# trig2_board.net
KiCad netlist of a schematic drawn in EAGLE
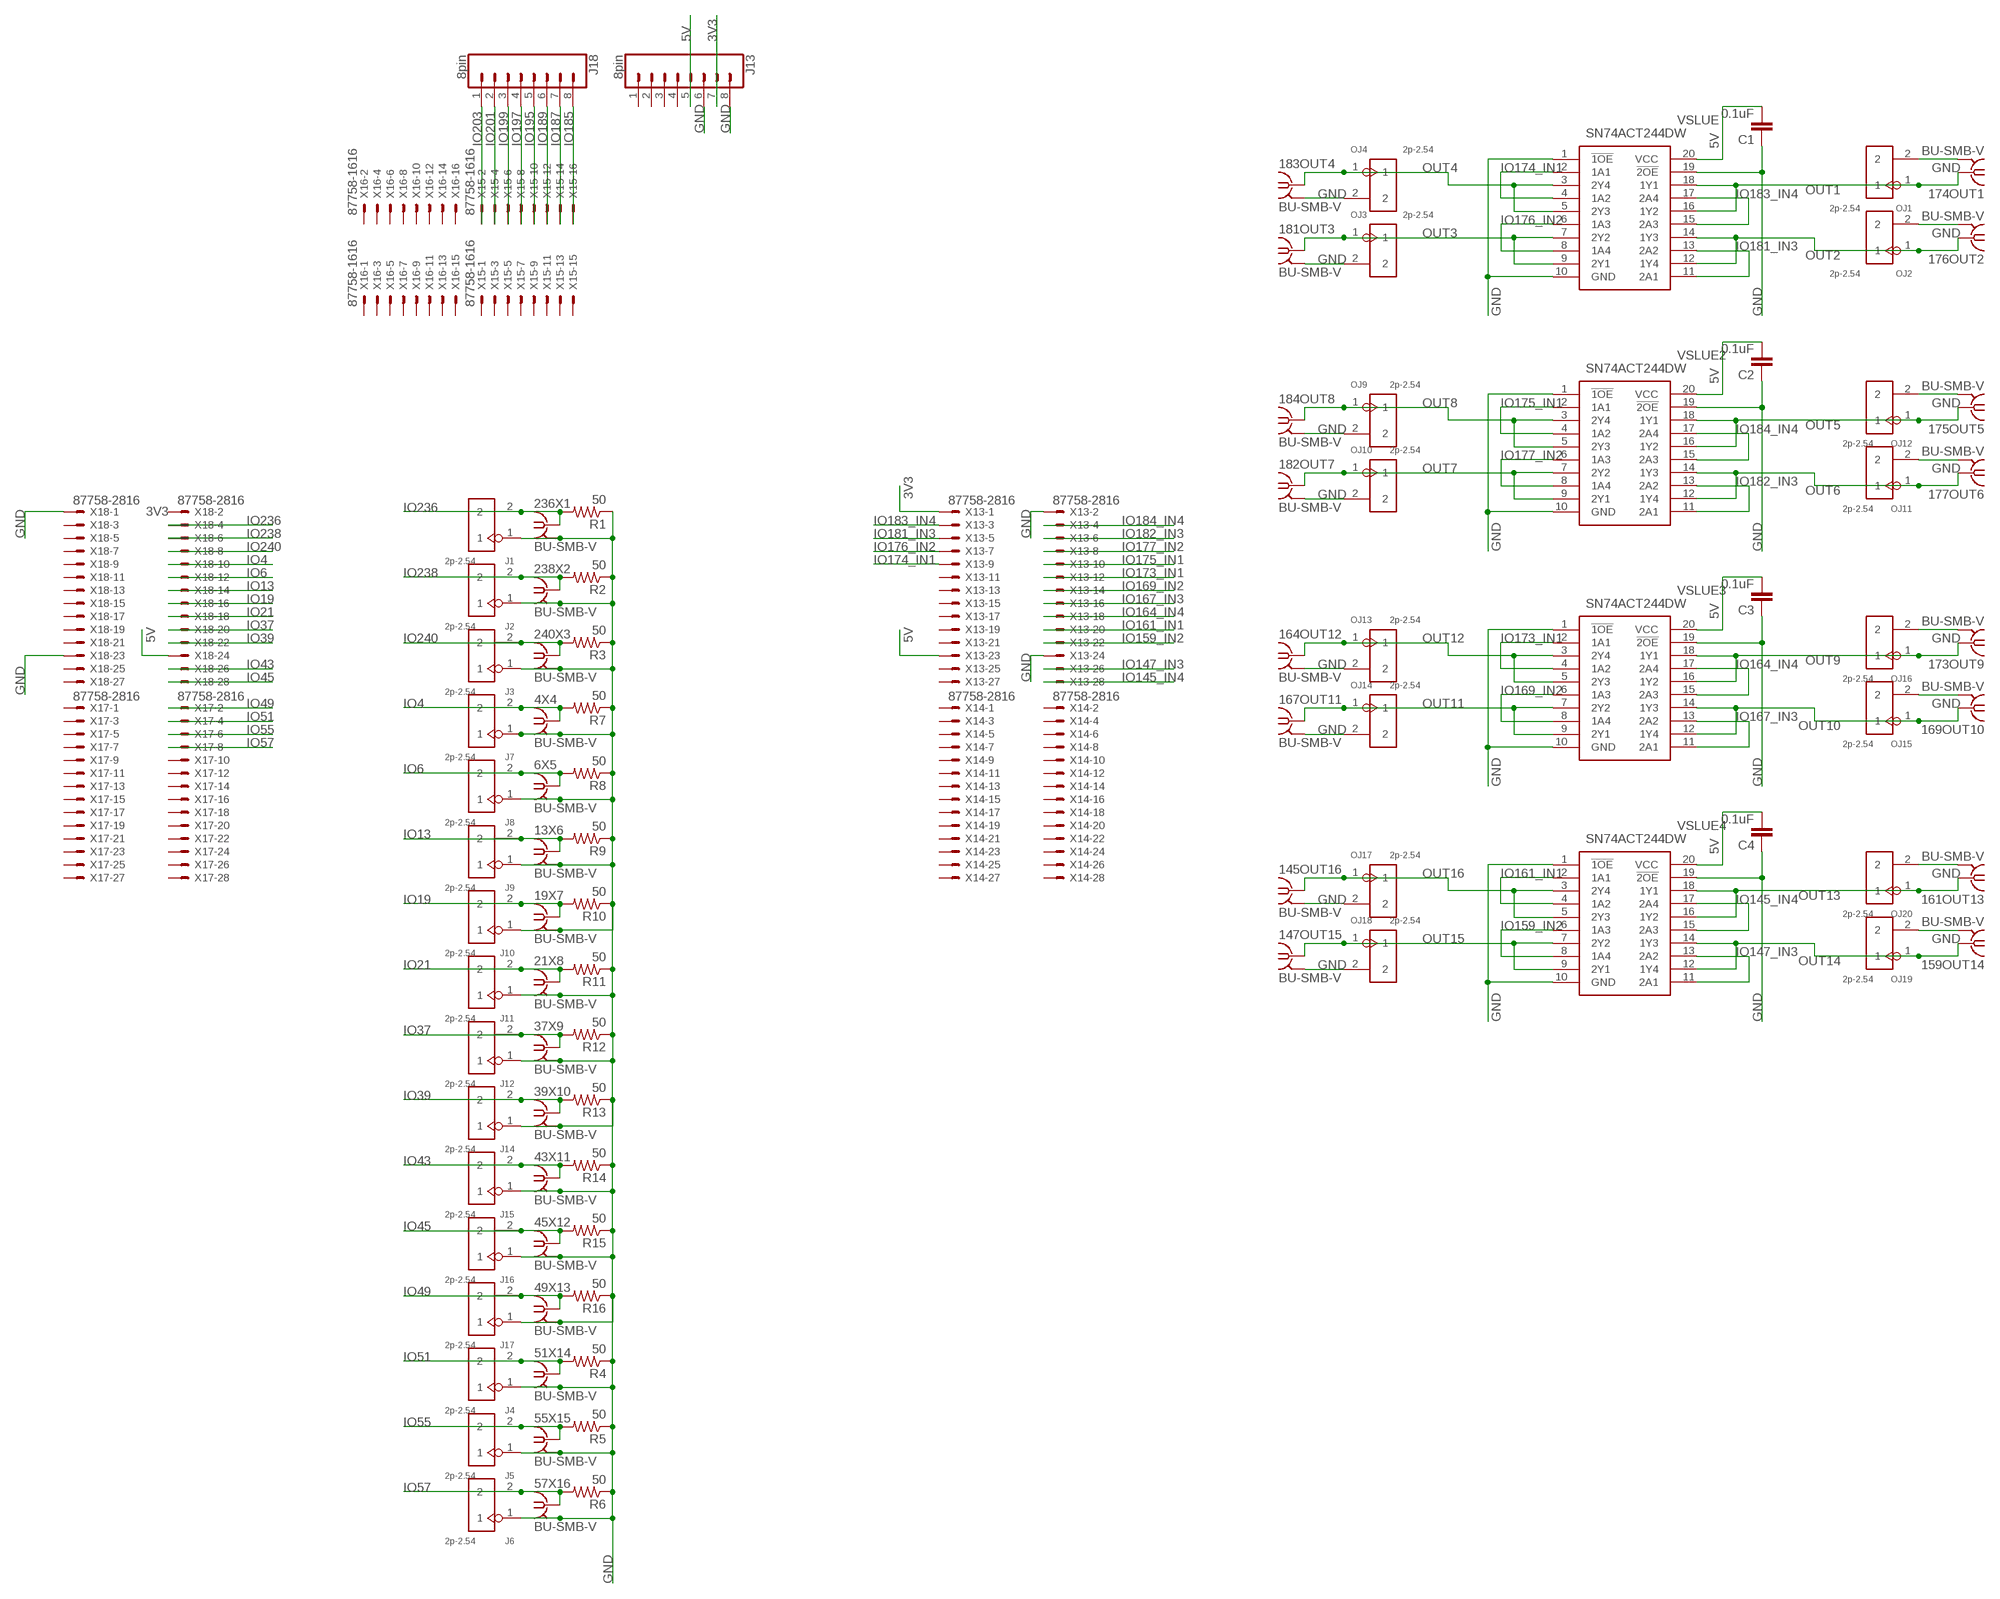
[diagram p0: schematic, sheet 1]

(export (version "E")
  (design (tool "Eeschema 10.0.6"))
  (components
    (comp (ref "4X4")
      (value "BU-SMB-V")
      (footprint "eagle-import:BU-SMB-V")
      (libsource (lib "eagle-import") (part "BU-SMB-V"))
    )
    (comp (ref "6X5")
      (value "BU-SMB-V")
      (footprint "eagle-import:BU-SMB-V")
      (libsource (lib "eagle-import") (part "BU-SMB-V"))
    )
    (comp (ref "13X6")
      (value "BU-SMB-V")
      (footprint "eagle-import:BU-SMB-V")
      (libsource (lib "eagle-import") (part "BU-SMB-V"))
    )
    (comp (ref "19X7")
      (value "BU-SMB-V")
      (footprint "eagle-import:BU-SMB-V")
      (libsource (lib "eagle-import") (part "BU-SMB-V"))
    )
    (comp (ref "21X8")
      (value "BU-SMB-V")
      (footprint "eagle-import:BU-SMB-V")
      (libsource (lib "eagle-import") (part "BU-SMB-V"))
    )
    (comp (ref "37X9")
      (value "BU-SMB-V")
      (footprint "eagle-import:BU-SMB-V")
      (libsource (lib "eagle-import") (part "BU-SMB-V"))
    )
    (comp (ref "39X10")
      (value "BU-SMB-V")
      (footprint "eagle-import:BU-SMB-V")
      (libsource (lib "eagle-import") (part "BU-SMB-V"))
    )
    (comp (ref "43X11")
      (value "BU-SMB-V")
      (footprint "eagle-import:BU-SMB-V")
      (libsource (lib "eagle-import") (part "BU-SMB-V"))
    )
    (comp (ref "45X12")
      (value "BU-SMB-V")
      (footprint "eagle-import:BU-SMB-V")
      (libsource (lib "eagle-import") (part "BU-SMB-V"))
    )
    (comp (ref "49X13")
      (value "BU-SMB-V")
      (footprint "eagle-import:BU-SMB-V")
      (libsource (lib "eagle-import") (part "BU-SMB-V"))
    )
    (comp (ref "51X14")
      (value "BU-SMB-V")
      (footprint "eagle-import:BU-SMB-V")
      (libsource (lib "eagle-import") (part "BU-SMB-V"))
    )
    (comp (ref "55X15")
      (value "BU-SMB-V")
      (footprint "eagle-import:BU-SMB-V")
      (libsource (lib "eagle-import") (part "BU-SMB-V"))
    )
    (comp (ref "57X16")
      (value "BU-SMB-V")
      (footprint "eagle-import:BU-SMB-V")
      (libsource (lib "eagle-import") (part "BU-SMB-V"))
    )
    (comp (ref "145OUT16")
      (value "BU-SMB-V")
      (footprint "eagle-import:BU-SMB-V")
      (libsource (lib "eagle-import") (part "BU-SMB-V"))
    )
    (comp (ref "147OUT15")
      (value "BU-SMB-V")
      (footprint "eagle-import:BU-SMB-V")
      (libsource (lib "eagle-import") (part "BU-SMB-V"))
    )
    (comp (ref "159OUT14")
      (value "BU-SMB-V")
      (footprint "eagle-import:BU-SMB-V")
      (libsource (lib "eagle-import") (part "BU-SMB-V"))
    )
    (comp (ref "161OUT13")
      (value "BU-SMB-V")
      (footprint "eagle-import:BU-SMB-V")
      (libsource (lib "eagle-import") (part "BU-SMB-V"))
    )
    (comp (ref "164OUT12")
      (value "BU-SMB-V")
      (footprint "eagle-import:BU-SMB-V")
      (libsource (lib "eagle-import") (part "BU-SMB-V"))
    )
    (comp (ref "167OUT11")
      (value "BU-SMB-V")
      (footprint "eagle-import:BU-SMB-V")
      (libsource (lib "eagle-import") (part "BU-SMB-V"))
    )
    (comp (ref "169OUT10")
      (value "BU-SMB-V")
      (footprint "eagle-import:BU-SMB-V")
      (libsource (lib "eagle-import") (part "BU-SMB-V"))
    )
    (comp (ref "173OUT9")
      (value "BU-SMB-V")
      (footprint "eagle-import:BU-SMB-V")
      (libsource (lib "eagle-import") (part "BU-SMB-V"))
    )
    (comp (ref "174OUT1")
      (value "BU-SMB-V")
      (footprint "eagle-import:BU-SMB-V")
      (libsource (lib "eagle-import") (part "BU-SMB-V"))
    )
    (comp (ref "175OUT5")
      (value "BU-SMB-V")
      (footprint "eagle-import:BU-SMB-V")
      (libsource (lib "eagle-import") (part "BU-SMB-V"))
    )
    (comp (ref "176OUT2")
      (value "BU-SMB-V")
      (footprint "eagle-import:BU-SMB-V")
      (libsource (lib "eagle-import") (part "BU-SMB-V"))
    )
    (comp (ref "177OUT6")
      (value "BU-SMB-V")
      (footprint "eagle-import:BU-SMB-V")
      (libsource (lib "eagle-import") (part "BU-SMB-V"))
    )
    (comp (ref "181OUT3")
      (value "BU-SMB-V")
      (footprint "eagle-import:BU-SMB-V")
      (libsource (lib "eagle-import") (part "BU-SMB-V"))
    )
    (comp (ref "182OUT7")
      (value "BU-SMB-V")
      (footprint "eagle-import:BU-SMB-V")
      (libsource (lib "eagle-import") (part "BU-SMB-V"))
    )
    (comp (ref "183OUT4")
      (value "BU-SMB-V")
      (footprint "eagle-import:BU-SMB-V")
      (libsource (lib "eagle-import") (part "BU-SMB-V"))
    )
    (comp (ref "184OUT8")
      (value "BU-SMB-V")
      (footprint "eagle-import:BU-SMB-V")
      (libsource (lib "eagle-import") (part "BU-SMB-V"))
    )
    (comp (ref "236X1")
      (value "BU-SMB-V")
      (footprint "eagle-import:BU-SMB-V")
      (libsource (lib "eagle-import") (part "BU-SMB-V"))
    )
    (comp (ref "238X2")
      (value "BU-SMB-V")
      (footprint "eagle-import:BU-SMB-V")
      (libsource (lib "eagle-import") (part "BU-SMB-V"))
    )
    (comp (ref "240X3")
      (value "BU-SMB-V")
      (footprint "eagle-import:BU-SMB-V")
      (libsource (lib "eagle-import") (part "BU-SMB-V"))
    )
    (comp (ref "C1")
      (value "0.1uF")
      (footprint "eagle-import:0805")
      (libsource (lib "eagle-import") (part "CAP0805"))
    )
    (comp (ref "C2")
      (value "0.1uF")
      (footprint "eagle-import:0805")
      (libsource (lib "eagle-import") (part "CAP0805"))
    )
    (comp (ref "C3")
      (value "0.1uF")
      (footprint "eagle-import:0805")
      (libsource (lib "eagle-import") (part "CAP0805"))
    )
    (comp (ref "C4")
      (value "0.1uF")
      (footprint "eagle-import:0805")
      (libsource (lib "eagle-import") (part "CAP0805"))
    )
    (comp (ref "J1")
      (value "2p-2.54")
      (footprint "eagle-import:H2-2.54")
      (fields (field (name "MPN") "P125-1102A0BS116A1"))
      (libsource (lib "eagle-import") (part "DIP-BLACK-MALE-HEADER-VERT(2P-2.54)"))
    )
    (comp (ref "J2")
      (value "2p-2.54")
      (footprint "eagle-import:H2-2.54")
      (fields (field (name "MPN") "P125-1102A0BS116A1"))
      (libsource (lib "eagle-import") (part "DIP-BLACK-MALE-HEADER-VERT(2P-2.54)"))
    )
    (comp (ref "J3")
      (value "2p-2.54")
      (footprint "eagle-import:H2-2.54")
      (fields (field (name "MPN") "P125-1102A0BS116A1"))
      (libsource (lib "eagle-import") (part "DIP-BLACK-MALE-HEADER-VERT(2P-2.54)"))
    )
    (comp (ref "J4")
      (value "2p-2.54")
      (footprint "eagle-import:H2-2.54")
      (fields (field (name "MPN") "P125-1102A0BS116A1"))
      (libsource (lib "eagle-import") (part "DIP-BLACK-MALE-HEADER-VERT(2P-2.54)"))
    )
    (comp (ref "J5")
      (value "2p-2.54")
      (footprint "eagle-import:H2-2.54")
      (fields (field (name "MPN") "P125-1102A0BS116A1"))
      (libsource (lib "eagle-import") (part "DIP-BLACK-MALE-HEADER-VERT(2P-2.54)"))
    )
    (comp (ref "J6")
      (value "2p-2.54")
      (footprint "eagle-import:H2-2.54")
      (fields (field (name "MPN") "P125-1102A0BS116A1"))
      (libsource (lib "eagle-import") (part "DIP-BLACK-MALE-HEADER-VERT(2P-2.54)"))
    )
    (comp (ref "J7")
      (value "2p-2.54")
      (footprint "eagle-import:H2-2.54")
      (fields (field (name "MPN") "P125-1102A0BS116A1"))
      (libsource (lib "eagle-import") (part "DIP-BLACK-MALE-HEADER-VERT(2P-2.54)"))
    )
    (comp (ref "J8")
      (value "2p-2.54")
      (footprint "eagle-import:H2-2.54")
      (fields (field (name "MPN") "P125-1102A0BS116A1"))
      (libsource (lib "eagle-import") (part "DIP-BLACK-MALE-HEADER-VERT(2P-2.54)"))
    )
    (comp (ref "J9")
      (value "2p-2.54")
      (footprint "eagle-import:H2-2.54")
      (fields (field (name "MPN") "P125-1102A0BS116A1"))
      (libsource (lib "eagle-import") (part "DIP-BLACK-MALE-HEADER-VERT(2P-2.54)"))
    )
    (comp (ref "J10")
      (value "2p-2.54")
      (footprint "eagle-import:H2-2.54")
      (fields (field (name "MPN") "P125-1102A0BS116A1"))
      (libsource (lib "eagle-import") (part "DIP-BLACK-MALE-HEADER-VERT(2P-2.54)"))
    )
    (comp (ref "J11")
      (value "2p-2.54")
      (footprint "eagle-import:H2-2.54")
      (fields (field (name "MPN") "P125-1102A0BS116A1"))
      (libsource (lib "eagle-import") (part "DIP-BLACK-MALE-HEADER-VERT(2P-2.54)"))
    )
    (comp (ref "J12")
      (value "2p-2.54")
      (footprint "eagle-import:H2-2.54")
      (fields (field (name "MPN") "P125-1102A0BS116A1"))
      (libsource (lib "eagle-import") (part "DIP-BLACK-MALE-HEADER-VERT(2P-2.54)"))
    )
    (comp (ref "J13")
      (value "8pin")
      (footprint "eagle-import:1X08")
      (libsource (lib "eagle-import") (part "CONN_08{dblquote}"))
    )
    (comp (ref "J14")
      (value "2p-2.54")
      (footprint "eagle-import:H2-2.54")
      (fields (field (name "MPN") "P125-1102A0BS116A1"))
      (libsource (lib "eagle-import") (part "DIP-BLACK-MALE-HEADER-VERT(2P-2.54)"))
    )
    (comp (ref "J15")
      (value "2p-2.54")
      (footprint "eagle-import:H2-2.54")
      (fields (field (name "MPN") "P125-1102A0BS116A1"))
      (libsource (lib "eagle-import") (part "DIP-BLACK-MALE-HEADER-VERT(2P-2.54)"))
    )
    (comp (ref "J16")
      (value "2p-2.54")
      (footprint "eagle-import:H2-2.54")
      (fields (field (name "MPN") "P125-1102A0BS116A1"))
      (libsource (lib "eagle-import") (part "DIP-BLACK-MALE-HEADER-VERT(2P-2.54)"))
    )
    (comp (ref "J17")
      (value "2p-2.54")
      (footprint "eagle-import:H2-2.54")
      (fields (field (name "MPN") "P125-1102A0BS116A1"))
      (libsource (lib "eagle-import") (part "DIP-BLACK-MALE-HEADER-VERT(2P-2.54)"))
    )
    (comp (ref "J18")
      (value "8pin")
      (footprint "eagle-import:1X08")
      (libsource (lib "eagle-import") (part "CONN_08{dblquote}"))
    )
    (comp (ref "OJ1")
      (value "2p-2.54")
      (footprint "eagle-import:H2-2.54")
      (fields (field (name "MPN") "P125-1102A0BS116A1"))
      (libsource (lib "eagle-import") (part "DIP-BLACK-MALE-HEADER-VERT(2P-2.54)"))
    )
    (comp (ref "OJ2")
      (value "2p-2.54")
      (footprint "eagle-import:H2-2.54")
      (fields (field (name "MPN") "P125-1102A0BS116A1"))
      (libsource (lib "eagle-import") (part "DIP-BLACK-MALE-HEADER-VERT(2P-2.54)"))
    )
    (comp (ref "OJ3")
      (value "2p-2.54")
      (footprint "eagle-import:H2-2.54")
      (fields (field (name "MPN") "P125-1102A0BS116A1"))
      (libsource (lib "eagle-import") (part "DIP-BLACK-MALE-HEADER-VERT(2P-2.54)"))
    )
    (comp (ref "OJ4")
      (value "2p-2.54")
      (footprint "eagle-import:H2-2.54")
      (fields (field (name "MPN") "P125-1102A0BS116A1"))
      (libsource (lib "eagle-import") (part "DIP-BLACK-MALE-HEADER-VERT(2P-2.54)"))
    )
    (comp (ref "OJ9")
      (value "2p-2.54")
      (footprint "eagle-import:H2-2.54")
      (fields (field (name "MPN") "P125-1102A0BS116A1"))
      (libsource (lib "eagle-import") (part "DIP-BLACK-MALE-HEADER-VERT(2P-2.54)"))
    )
    (comp (ref "OJ10")
      (value "2p-2.54")
      (footprint "eagle-import:H2-2.54")
      (fields (field (name "MPN") "P125-1102A0BS116A1"))
      (libsource (lib "eagle-import") (part "DIP-BLACK-MALE-HEADER-VERT(2P-2.54)"))
    )
    (comp (ref "OJ11")
      (value "2p-2.54")
      (footprint "eagle-import:H2-2.54")
      (fields (field (name "MPN") "P125-1102A0BS116A1"))
      (libsource (lib "eagle-import") (part "DIP-BLACK-MALE-HEADER-VERT(2P-2.54)"))
    )
    (comp (ref "OJ12")
      (value "2p-2.54")
      (footprint "eagle-import:H2-2.54")
      (fields (field (name "MPN") "P125-1102A0BS116A1"))
      (libsource (lib "eagle-import") (part "DIP-BLACK-MALE-HEADER-VERT(2P-2.54)"))
    )
    (comp (ref "OJ13")
      (value "2p-2.54")
      (footprint "eagle-import:H2-2.54")
      (fields (field (name "MPN") "P125-1102A0BS116A1"))
      (libsource (lib "eagle-import") (part "DIP-BLACK-MALE-HEADER-VERT(2P-2.54)"))
    )
    (comp (ref "OJ14")
      (value "2p-2.54")
      (footprint "eagle-import:H2-2.54")
      (fields (field (name "MPN") "P125-1102A0BS116A1"))
      (libsource (lib "eagle-import") (part "DIP-BLACK-MALE-HEADER-VERT(2P-2.54)"))
    )
    (comp (ref "OJ15")
      (value "2p-2.54")
      (footprint "eagle-import:H2-2.54")
      (fields (field (name "MPN") "P125-1102A0BS116A1"))
      (libsource (lib "eagle-import") (part "DIP-BLACK-MALE-HEADER-VERT(2P-2.54)"))
    )
    (comp (ref "OJ16")
      (value "2p-2.54")
      (footprint "eagle-import:H2-2.54")
      (fields (field (name "MPN") "P125-1102A0BS116A1"))
      (libsource (lib "eagle-import") (part "DIP-BLACK-MALE-HEADER-VERT(2P-2.54)"))
    )
    (comp (ref "OJ17")
      (value "2p-2.54")
      (footprint "eagle-import:H2-2.54")
      (fields (field (name "MPN") "P125-1102A0BS116A1"))
      (libsource (lib "eagle-import") (part "DIP-BLACK-MALE-HEADER-VERT(2P-2.54)"))
    )
    (comp (ref "OJ18")
      (value "2p-2.54")
      (footprint "eagle-import:H2-2.54")
      (fields (field (name "MPN") "P125-1102A0BS116A1"))
      (libsource (lib "eagle-import") (part "DIP-BLACK-MALE-HEADER-VERT(2P-2.54)"))
    )
    (comp (ref "OJ19")
      (value "2p-2.54")
      (footprint "eagle-import:H2-2.54")
      (fields (field (name "MPN") "P125-1102A0BS116A1"))
      (libsource (lib "eagle-import") (part "DIP-BLACK-MALE-HEADER-VERT(2P-2.54)"))
    )
    (comp (ref "OJ20")
      (value "2p-2.54")
      (footprint "eagle-import:H2-2.54")
      (fields (field (name "MPN") "P125-1102A0BS116A1"))
      (libsource (lib "eagle-import") (part "DIP-BLACK-MALE-HEADER-VERT(2P-2.54)"))
    )
    (comp (ref "R1")
      (value "50")
      (footprint "eagle-import:AXIAL-0.3")
      (libsource (lib "eagle-import") (part "RESISTORAXIAL-0.3"))
    )
    (comp (ref "R2")
      (value "50")
      (footprint "eagle-import:AXIAL-0.3")
      (libsource (lib "eagle-import") (part "RESISTORAXIAL-0.3"))
    )
    (comp (ref "R3")
      (value "50")
      (footprint "eagle-import:AXIAL-0.3")
      (libsource (lib "eagle-import") (part "RESISTORAXIAL-0.3"))
    )
    (comp (ref "R4")
      (value "50")
      (footprint "eagle-import:AXIAL-0.3")
      (libsource (lib "eagle-import") (part "RESISTORAXIAL-0.3"))
    )
    (comp (ref "R5")
      (value "50")
      (footprint "eagle-import:AXIAL-0.3")
      (libsource (lib "eagle-import") (part "RESISTORAXIAL-0.3"))
    )
    (comp (ref "R6")
      (value "50")
      (footprint "eagle-import:AXIAL-0.3")
      (libsource (lib "eagle-import") (part "RESISTORAXIAL-0.3"))
    )
    (comp (ref "R7")
      (value "50")
      (footprint "eagle-import:AXIAL-0.3")
      (libsource (lib "eagle-import") (part "RESISTORAXIAL-0.3"))
    )
    (comp (ref "R8")
      (value "50")
      (footprint "eagle-import:AXIAL-0.3")
      (libsource (lib "eagle-import") (part "RESISTORAXIAL-0.3"))
    )
    (comp (ref "R9")
      (value "50")
      (footprint "eagle-import:AXIAL-0.3")
      (libsource (lib "eagle-import") (part "RESISTORAXIAL-0.3"))
    )
    (comp (ref "R10")
      (value "50")
      (footprint "eagle-import:AXIAL-0.3")
      (libsource (lib "eagle-import") (part "RESISTORAXIAL-0.3"))
    )
    (comp (ref "R11")
      (value "50")
      (footprint "eagle-import:AXIAL-0.3")
      (libsource (lib "eagle-import") (part "RESISTORAXIAL-0.3"))
    )
    (comp (ref "R12")
      (value "50")
      (footprint "eagle-import:AXIAL-0.3")
      (libsource (lib "eagle-import") (part "RESISTORAXIAL-0.3"))
    )
    (comp (ref "R13")
      (value "50")
      (footprint "eagle-import:AXIAL-0.3")
      (libsource (lib "eagle-import") (part "RESISTORAXIAL-0.3"))
    )
    (comp (ref "R14")
      (value "50")
      (footprint "eagle-import:AXIAL-0.3")
      (libsource (lib "eagle-import") (part "RESISTORAXIAL-0.3"))
    )
    (comp (ref "R15")
      (value "50")
      (footprint "eagle-import:AXIAL-0.3")
      (libsource (lib "eagle-import") (part "RESISTORAXIAL-0.3"))
    )
    (comp (ref "R16")
      (value "50")
      (footprint "eagle-import:AXIAL-0.3")
      (libsource (lib "eagle-import") (part "RESISTORAXIAL-0.3"))
    )
    (comp (ref "VSLUE")
      (value "SN74ACT244DW")
      (footprint "eagle-import:SOIC127P1030X265-20N")
      (fields (field (name "RS_PART_NUMBER") "4363169"))
      (libsource (lib "eagle-import") (part "SN74ACT244DW"))
    )
    (comp (ref "VSLUE2")
      (value "SN74ACT244DW")
      (footprint "eagle-import:SOIC127P1030X265-20N")
      (fields (field (name "RS_PART_NUMBER") "4363169"))
      (libsource (lib "eagle-import") (part "SN74ACT244DW"))
    )
    (comp (ref "VSLUE3")
      (value "SN74ACT244DW")
      (footprint "eagle-import:SOIC127P1030X265-20N")
      (fields (field (name "RS_PART_NUMBER") "4363169"))
      (libsource (lib "eagle-import") (part "SN74ACT244DW"))
    )
    (comp (ref "VSLUE4")
      (value "SN74ACT244DW")
      (footprint "eagle-import:SOIC127P1030X265-20N")
      (fields (field (name "RS_PART_NUMBER") "4363169"))
      (libsource (lib "eagle-import") (part "SN74ACT244DW"))
    )
    (comp (ref "X13")
      (value "87758-2816")
      (footprint "eagle-import:87758-2816")
      (fields (field (name "MF") "MOLEX"))
      (libsource (lib "eagle-import") (part "87758-2816"))
    )
    (comp (ref "X14")
      (value "87758-2816")
      (footprint "eagle-import:87758-2816")
      (fields (field (name "MF") "MOLEX"))
      (libsource (lib "eagle-import") (part "87758-2816"))
    )
    (comp (ref "X15")
      (value "87758-1616")
      (footprint "eagle-import:87758-1616")
      (fields (field (name "MF") "MOLEX"))
      (libsource (lib "eagle-import") (part "87758-1616"))
    )
    (comp (ref "X16")
      (value "87758-1616")
      (footprint "eagle-import:87758-1616")
      (fields (field (name "MF") "MOLEX"))
      (libsource (lib "eagle-import") (part "87758-1616"))
    )
    (comp (ref "X17")
      (value "87758-2816")
      (footprint "eagle-import:87758-2816")
      (fields (field (name "MF") "MOLEX"))
      (libsource (lib "eagle-import") (part "87758-2816"))
    )
    (comp (ref "X18")
      (value "87758-2816")
      (footprint "eagle-import:87758-2816")
      (fields (field (name "MF") "MOLEX"))
      (libsource (lib "eagle-import") (part "87758-2816"))
    )
  )
  (nets
    (net (code "1") (name "/3V3") (class "Default")
      (node (ref "J13") (pin "7") (pinfunction "7_7") (pintype "passive"))
      (node (ref "X13") (pin "1") (pinfunction "S_1") (pintype "passive"))
    )
    (net (code "2") (name "/5V") (class "Default")
      (node (ref "C1") (pin "2") (pinfunction "2_2") (pintype "passive"))
      (node (ref "C2") (pin "2") (pinfunction "2_2") (pintype "passive"))
      (node (ref "C3") (pin "2") (pinfunction "2_2") (pintype "passive"))
      (node (ref "C4") (pin "2") (pinfunction "2_2") (pintype "passive"))
      (node (ref "J13") (pin "5") (pinfunction "5_5") (pintype "passive"))
      (node (ref "VSLUE") (pin "20") (pinfunction "VCC_20") (pintype "power_in"))
      (node (ref "VSLUE2") (pin "20") (pinfunction "VCC_20") (pintype "power_in"))
      (node (ref "VSLUE3") (pin "20") (pinfunction "VCC_20") (pintype "power_in"))
      (node (ref "VSLUE4") (pin "20") (pinfunction "VCC_20") (pintype "power_in"))
      (node (ref "X13") (pin "23") (pinfunction "S_23") (pintype "passive"))
      (node (ref "X18") (pin "24") (pinfunction "S_24") (pintype "passive"))
    )
    (net (code "3") (name "/GND") (class "Default")
      (node (ref "13X6") (pin "2") (pinfunction "2_2") (pintype "passive"))
      (node (ref "13X6") (pin "3") (pinfunction "2_3") (pintype "passive"))
      (node (ref "13X6") (pin "4") (pinfunction "2_4") (pintype "passive"))
      (node (ref "13X6") (pin "5") (pinfunction "2_5") (pintype "passive"))
      (node (ref "145OUT16") (pin "2") (pinfunction "2_2") (pintype "passive"))
      (node (ref "145OUT16") (pin "3") (pinfunction "2_3") (pintype "passive"))
      (node (ref "145OUT16") (pin "4") (pinfunction "2_4") (pintype "passive"))
      (node (ref "145OUT16") (pin "5") (pinfunction "2_5") (pintype "passive"))
      (node (ref "147OUT15") (pin "2") (pinfunction "2_2") (pintype "passive"))
      (node (ref "147OUT15") (pin "3") (pinfunction "2_3") (pintype "passive"))
      (node (ref "147OUT15") (pin "4") (pinfunction "2_4") (pintype "passive"))
      (node (ref "147OUT15") (pin "5") (pinfunction "2_5") (pintype "passive"))
      (node (ref "159OUT14") (pin "2") (pinfunction "2_2") (pintype "passive"))
      (node (ref "159OUT14") (pin "3") (pinfunction "2_3") (pintype "passive"))
      (node (ref "159OUT14") (pin "4") (pinfunction "2_4") (pintype "passive"))
      (node (ref "159OUT14") (pin "5") (pinfunction "2_5") (pintype "passive"))
      (node (ref "161OUT13") (pin "2") (pinfunction "2_2") (pintype "passive"))
      (node (ref "161OUT13") (pin "3") (pinfunction "2_3") (pintype "passive"))
      (node (ref "161OUT13") (pin "4") (pinfunction "2_4") (pintype "passive"))
      (node (ref "161OUT13") (pin "5") (pinfunction "2_5") (pintype "passive"))
      (node (ref "164OUT12") (pin "2") (pinfunction "2_2") (pintype "passive"))
      (node (ref "164OUT12") (pin "3") (pinfunction "2_3") (pintype "passive"))
      (node (ref "164OUT12") (pin "4") (pinfunction "2_4") (pintype "passive"))
      (node (ref "164OUT12") (pin "5") (pinfunction "2_5") (pintype "passive"))
      (node (ref "167OUT11") (pin "2") (pinfunction "2_2") (pintype "passive"))
      (node (ref "167OUT11") (pin "3") (pinfunction "2_3") (pintype "passive"))
      (node (ref "167OUT11") (pin "4") (pinfunction "2_4") (pintype "passive"))
      (node (ref "167OUT11") (pin "5") (pinfunction "2_5") (pintype "passive"))
      (node (ref "169OUT10") (pin "2") (pinfunction "2_2") (pintype "passive"))
      (node (ref "169OUT10") (pin "3") (pinfunction "2_3") (pintype "passive"))
      (node (ref "169OUT10") (pin "4") (pinfunction "2_4") (pintype "passive"))
      (node (ref "169OUT10") (pin "5") (pinfunction "2_5") (pintype "passive"))
      (node (ref "173OUT9") (pin "2") (pinfunction "2_2") (pintype "passive"))
      (node (ref "173OUT9") (pin "3") (pinfunction "2_3") (pintype "passive"))
      (node (ref "173OUT9") (pin "4") (pinfunction "2_4") (pintype "passive"))
      (node (ref "173OUT9") (pin "5") (pinfunction "2_5") (pintype "passive"))
      (node (ref "174OUT1") (pin "2") (pinfunction "2_2") (pintype "passive"))
      (node (ref "174OUT1") (pin "3") (pinfunction "2_3") (pintype "passive"))
      (node (ref "174OUT1") (pin "4") (pinfunction "2_4") (pintype "passive"))
      (node (ref "174OUT1") (pin "5") (pinfunction "2_5") (pintype "passive"))
      (node (ref "175OUT5") (pin "2") (pinfunction "2_2") (pintype "passive"))
      (node (ref "175OUT5") (pin "3") (pinfunction "2_3") (pintype "passive"))
      (node (ref "175OUT5") (pin "4") (pinfunction "2_4") (pintype "passive"))
      (node (ref "175OUT5") (pin "5") (pinfunction "2_5") (pintype "passive"))
      (node (ref "176OUT2") (pin "2") (pinfunction "2_2") (pintype "passive"))
      (node (ref "176OUT2") (pin "3") (pinfunction "2_3") (pintype "passive"))
      (node (ref "176OUT2") (pin "4") (pinfunction "2_4") (pintype "passive"))
      (node (ref "176OUT2") (pin "5") (pinfunction "2_5") (pintype "passive"))
      (node (ref "177OUT6") (pin "2") (pinfunction "2_2") (pintype "passive"))
      (node (ref "177OUT6") (pin "3") (pinfunction "2_3") (pintype "passive"))
      (node (ref "177OUT6") (pin "4") (pinfunction "2_4") (pintype "passive"))
      (node (ref "177OUT6") (pin "5") (pinfunction "2_5") (pintype "passive"))
      (node (ref "181OUT3") (pin "2") (pinfunction "2_2") (pintype "passive"))
      (node (ref "181OUT3") (pin "3") (pinfunction "2_3") (pintype "passive"))
      (node (ref "181OUT3") (pin "4") (pinfunction "2_4") (pintype "passive"))
      (node (ref "181OUT3") (pin "5") (pinfunction "2_5") (pintype "passive"))
      (node (ref "182OUT7") (pin "2") (pinfunction "2_2") (pintype "passive"))
      (node (ref "182OUT7") (pin "3") (pinfunction "2_3") (pintype "passive"))
      (node (ref "182OUT7") (pin "4") (pinfunction "2_4") (pintype "passive"))
      (node (ref "182OUT7") (pin "5") (pinfunction "2_5") (pintype "passive"))
      (node (ref "183OUT4") (pin "2") (pinfunction "2_2") (pintype "passive"))
      (node (ref "183OUT4") (pin "3") (pinfunction "2_3") (pintype "passive"))
      (node (ref "183OUT4") (pin "4") (pinfunction "2_4") (pintype "passive"))
      (node (ref "183OUT4") (pin "5") (pinfunction "2_5") (pintype "passive"))
      (node (ref "184OUT8") (pin "2") (pinfunction "2_2") (pintype "passive"))
      (node (ref "184OUT8") (pin "3") (pinfunction "2_3") (pintype "passive"))
      (node (ref "184OUT8") (pin "4") (pinfunction "2_4") (pintype "passive"))
      (node (ref "184OUT8") (pin "5") (pinfunction "2_5") (pintype "passive"))
      (node (ref "19X7") (pin "2") (pinfunction "2_2") (pintype "passive"))
      (node (ref "19X7") (pin "3") (pinfunction "2_3") (pintype "passive"))
      (node (ref "19X7") (pin "4") (pinfunction "2_4") (pintype "passive"))
      (node (ref "19X7") (pin "5") (pinfunction "2_5") (pintype "passive"))
      (node (ref "21X8") (pin "2") (pinfunction "2_2") (pintype "passive"))
      (node (ref "21X8") (pin "3") (pinfunction "2_3") (pintype "passive"))
      (node (ref "21X8") (pin "4") (pinfunction "2_4") (pintype "passive"))
      (node (ref "21X8") (pin "5") (pinfunction "2_5") (pintype "passive"))
      (node (ref "236X1") (pin "2") (pinfunction "2_2") (pintype "passive"))
      (node (ref "236X1") (pin "3") (pinfunction "2_3") (pintype "passive"))
      (node (ref "236X1") (pin "4") (pinfunction "2_4") (pintype "passive"))
      (node (ref "236X1") (pin "5") (pinfunction "2_5") (pintype "passive"))
      (node (ref "238X2") (pin "2") (pinfunction "2_2") (pintype "passive"))
      (node (ref "238X2") (pin "3") (pinfunction "2_3") (pintype "passive"))
      (node (ref "238X2") (pin "4") (pinfunction "2_4") (pintype "passive"))
      (node (ref "238X2") (pin "5") (pinfunction "2_5") (pintype "passive"))
      (node (ref "240X3") (pin "2") (pinfunction "2_2") (pintype "passive"))
      (node (ref "240X3") (pin "3") (pinfunction "2_3") (pintype "passive"))
      (node (ref "240X3") (pin "4") (pinfunction "2_4") (pintype "passive"))
      (node (ref "240X3") (pin "5") (pinfunction "2_5") (pintype "passive"))
      (node (ref "37X9") (pin "2") (pinfunction "2_2") (pintype "passive"))
      (node (ref "37X9") (pin "3") (pinfunction "2_3") (pintype "passive"))
      (node (ref "37X9") (pin "4") (pinfunction "2_4") (pintype "passive"))
      (node (ref "37X9") (pin "5") (pinfunction "2_5") (pintype "passive"))
      (node (ref "39X10") (pin "2") (pinfunction "2_2") (pintype "passive"))
      (node (ref "39X10") (pin "3") (pinfunction "2_3") (pintype "passive"))
      (node (ref "39X10") (pin "4") (pinfunction "2_4") (pintype "passive"))
      (node (ref "39X10") (pin "5") (pinfunction "2_5") (pintype "passive"))
      (node (ref "43X11") (pin "2") (pinfunction "2_2") (pintype "passive"))
      (node (ref "43X11") (pin "3") (pinfunction "2_3") (pintype "passive"))
      (node (ref "43X11") (pin "4") (pinfunction "2_4") (pintype "passive"))
      (node (ref "43X11") (pin "5") (pinfunction "2_5") (pintype "passive"))
      (node (ref "45X12") (pin "2") (pinfunction "2_2") (pintype "passive"))
      (node (ref "45X12") (pin "3") (pinfunction "2_3") (pintype "passive"))
      (node (ref "45X12") (pin "4") (pinfunction "2_4") (pintype "passive"))
      (node (ref "45X12") (pin "5") (pinfunction "2_5") (pintype "passive"))
      (node (ref "49X13") (pin "2") (pinfunction "2_2") (pintype "passive"))
      (node (ref "49X13") (pin "3") (pinfunction "2_3") (pintype "passive"))
      (node (ref "49X13") (pin "4") (pinfunction "2_4") (pintype "passive"))
      (node (ref "49X13") (pin "5") (pinfunction "2_5") (pintype "passive"))
      (node (ref "4X4") (pin "2") (pinfunction "2_2") (pintype "passive"))
      (node (ref "4X4") (pin "3") (pinfunction "2_3") (pintype "passive"))
      (node (ref "4X4") (pin "4") (pinfunction "2_4") (pintype "passive"))
      (node (ref "4X4") (pin "5") (pinfunction "2_5") (pintype "passive"))
      (node (ref "51X14") (pin "2") (pinfunction "2_2") (pintype "passive"))
      (node (ref "51X14") (pin "3") (pinfunction "2_3") (pintype "passive"))
      (node (ref "51X14") (pin "4") (pinfunction "2_4") (pintype "passive"))
      (node (ref "51X14") (pin "5") (pinfunction "2_5") (pintype "passive"))
      (node (ref "55X15") (pin "2") (pinfunction "2_2") (pintype "passive"))
      (node (ref "55X15") (pin "3") (pinfunction "2_3") (pintype "passive"))
      (node (ref "55X15") (pin "4") (pinfunction "2_4") (pintype "passive"))
      (node (ref "55X15") (pin "5") (pinfunction "2_5") (pintype "passive"))
      (node (ref "57X16") (pin "2") (pinfunction "2_2") (pintype "passive"))
      (node (ref "57X16") (pin "3") (pinfunction "2_3") (pintype "passive"))
      (node (ref "57X16") (pin "4") (pinfunction "2_4") (pintype "passive"))
      (node (ref "57X16") (pin "5") (pinfunction "2_5") (pintype "passive"))
      (node (ref "6X5") (pin "2") (pinfunction "2_2") (pintype "passive"))
      (node (ref "6X5") (pin "3") (pinfunction "2_3") (pintype "passive"))
      (node (ref "6X5") (pin "4") (pinfunction "2_4") (pintype "passive"))
      (node (ref "6X5") (pin "5") (pinfunction "2_5") (pintype "passive"))
      (node (ref "C1") (pin "1") (pinfunction "1_1") (pintype "passive"))
      (node (ref "C2") (pin "1") (pinfunction "1_1") (pintype "passive"))
      (node (ref "C3") (pin "1") (pinfunction "1_1") (pintype "passive"))
      (node (ref "C4") (pin "1") (pinfunction "1_1") (pintype "passive"))
      (node (ref "J1") (pin "1") (pinfunction "1_1") (pintype "bidirectional"))
      (node (ref "J10") (pin "1") (pinfunction "1_1") (pintype "bidirectional"))
      (node (ref "J11") (pin "1") (pinfunction "1_1") (pintype "bidirectional"))
      (node (ref "J12") (pin "1") (pinfunction "1_1") (pintype "bidirectional"))
      (node (ref "J13") (pin "6") (pinfunction "6_6") (pintype "passive"))
      (node (ref "J13") (pin "8") (pinfunction "8_8") (pintype "passive"))
      (node (ref "J14") (pin "1") (pinfunction "1_1") (pintype "bidirectional"))
      (node (ref "J15") (pin "1") (pinfunction "1_1") (pintype "bidirectional"))
      (node (ref "J16") (pin "1") (pinfunction "1_1") (pintype "bidirectional"))
      (node (ref "J17") (pin "1") (pinfunction "1_1") (pintype "bidirectional"))
      (node (ref "J2") (pin "1") (pinfunction "1_1") (pintype "bidirectional"))
      (node (ref "J3") (pin "1") (pinfunction "1_1") (pintype "bidirectional"))
      (node (ref "J4") (pin "1") (pinfunction "1_1") (pintype "bidirectional"))
      (node (ref "J5") (pin "1") (pinfunction "1_1") (pintype "bidirectional"))
      (node (ref "J6") (pin "1") (pinfunction "1_1") (pintype "bidirectional"))
      (node (ref "J7") (pin "1") (pinfunction "1_1") (pintype "bidirectional"))
      (node (ref "J8") (pin "1") (pinfunction "1_1") (pintype "bidirectional"))
      (node (ref "J9") (pin "1") (pinfunction "1_1") (pintype "bidirectional"))
      (node (ref "OJ1") (pin "2") (pinfunction "2_2") (pintype "bidirectional"))
      (node (ref "OJ10") (pin "2") (pinfunction "2_2") (pintype "bidirectional"))
      (node (ref "OJ11") (pin "2") (pinfunction "2_2") (pintype "bidirectional"))
      (node (ref "OJ12") (pin "2") (pinfunction "2_2") (pintype "bidirectional"))
      (node (ref "OJ13") (pin "2") (pinfunction "2_2") (pintype "bidirectional"))
      (node (ref "OJ14") (pin "2") (pinfunction "2_2") (pintype "bidirectional"))
      (node (ref "OJ15") (pin "2") (pinfunction "2_2") (pintype "bidirectional"))
      (node (ref "OJ16") (pin "2") (pinfunction "2_2") (pintype "bidirectional"))
      (node (ref "OJ17") (pin "2") (pinfunction "2_2") (pintype "bidirectional"))
      (node (ref "OJ18") (pin "2") (pinfunction "2_2") (pintype "bidirectional"))
      (node (ref "OJ19") (pin "2") (pinfunction "2_2") (pintype "bidirectional"))
      (node (ref "OJ2") (pin "2") (pinfunction "2_2") (pintype "bidirectional"))
      (node (ref "OJ20") (pin "2") (pinfunction "2_2") (pintype "bidirectional"))
      (node (ref "OJ3") (pin "2") (pinfunction "2_2") (pintype "bidirectional"))
      (node (ref "OJ4") (pin "2") (pinfunction "2_2") (pintype "bidirectional"))
      (node (ref "OJ9") (pin "2") (pinfunction "2_2") (pintype "bidirectional"))
      (node (ref "R1") (pin "P$1") (pinfunction "1_P$1") (pintype "passive"))
      (node (ref "R10") (pin "P$1") (pinfunction "1_P$1") (pintype "passive"))
      (node (ref "R11") (pin "P$1") (pinfunction "1_P$1") (pintype "passive"))
      (node (ref "R12") (pin "P$1") (pinfunction "1_P$1") (pintype "passive"))
      (node (ref "R13") (pin "P$1") (pinfunction "1_P$1") (pintype "passive"))
      (node (ref "R14") (pin "P$1") (pinfunction "1_P$1") (pintype "passive"))
      (node (ref "R15") (pin "P$1") (pinfunction "1_P$1") (pintype "passive"))
      (node (ref "R16") (pin "P$1") (pinfunction "1_P$1") (pintype "passive"))
      (node (ref "R2") (pin "P$1") (pinfunction "1_P$1") (pintype "passive"))
      (node (ref "R3") (pin "P$1") (pinfunction "1_P$1") (pintype "passive"))
      (node (ref "R4") (pin "P$1") (pinfunction "1_P$1") (pintype "passive"))
      (node (ref "R5") (pin "P$1") (pinfunction "1_P$1") (pintype "passive"))
      (node (ref "R6") (pin "P$1") (pinfunction "1_P$1") (pintype "passive"))
      (node (ref "R7") (pin "P$1") (pinfunction "1_P$1") (pintype "passive"))
      (node (ref "R8") (pin "P$1") (pinfunction "1_P$1") (pintype "passive"))
      (node (ref "R9") (pin "P$1") (pinfunction "1_P$1") (pintype "passive"))
      (node (ref "VSLUE") (pin "1") (pinfunction "~{1OE}_1") (pintype "input"))
      (node (ref "VSLUE") (pin "10") (pinfunction "GND_10") (pintype "power_in"))
      (node (ref "VSLUE") (pin "19") (pinfunction "~{2OE}_19") (pintype "input"))
      (node (ref "VSLUE2") (pin "1") (pinfunction "~{1OE}_1") (pintype "input"))
      (node (ref "VSLUE2") (pin "10") (pinfunction "GND_10") (pintype "power_in"))
      (node (ref "VSLUE2") (pin "19") (pinfunction "~{2OE}_19") (pintype "input"))
      (node (ref "VSLUE3") (pin "1") (pinfunction "~{1OE}_1") (pintype "input"))
      (node (ref "VSLUE3") (pin "10") (pinfunction "GND_10") (pintype "power_in"))
      (node (ref "VSLUE3") (pin "19") (pinfunction "~{2OE}_19") (pintype "input"))
      (node (ref "VSLUE4") (pin "1") (pinfunction "~{1OE}_1") (pintype "input"))
      (node (ref "VSLUE4") (pin "10") (pinfunction "GND_10") (pintype "power_in"))
      (node (ref "VSLUE4") (pin "19") (pinfunction "~{2OE}_19") (pintype "input"))
      (node (ref "X13") (pin "2") (pinfunction "S_2") (pintype "passive"))
      (node (ref "X13") (pin "24") (pinfunction "S_24") (pintype "passive"))
      (node (ref "X18") (pin "1") (pinfunction "S_1") (pintype "passive"))
      (node (ref "X18") (pin "23") (pinfunction "S_23") (pintype "passive"))
    )
    (net (code "4") (name "/IO4") (class "Default")
      (node (ref "4X4") (pin "1") (pinfunction "1_1") (pintype "passive"))
      (node (ref "J7") (pin "2") (pinfunction "2_2") (pintype "bidirectional"))
      (node (ref "R7") (pin "P$2") (pinfunction "2_P$2") (pintype "passive"))
      (node (ref "X18") (pin "10") (pinfunction "S_10") (pintype "passive"))
    )
    (net (code "5") (name "/IO6") (class "Default")
      (node (ref "6X5") (pin "1") (pinfunction "1_1") (pintype "passive"))
      (node (ref "J8") (pin "2") (pinfunction "2_2") (pintype "bidirectional"))
      (node (ref "R8") (pin "P$2") (pinfunction "2_P$2") (pintype "passive"))
      (node (ref "X18") (pin "12") (pinfunction "S_12") (pintype "passive"))
    )
    (net (code "6") (name "/IO13") (class "Default")
      (node (ref "13X6") (pin "1") (pinfunction "1_1") (pintype "passive"))
      (node (ref "J9") (pin "2") (pinfunction "2_2") (pintype "bidirectional"))
      (node (ref "R9") (pin "P$2") (pinfunction "2_P$2") (pintype "passive"))
      (node (ref "X18") (pin "14") (pinfunction "S_14") (pintype "passive"))
    )
    (net (code "7") (name "/IO19") (class "Default")
      (node (ref "19X7") (pin "1") (pinfunction "1_1") (pintype "passive"))
      (node (ref "J10") (pin "2") (pinfunction "2_2") (pintype "bidirectional"))
      (node (ref "R10") (pin "P$2") (pinfunction "2_P$2") (pintype "passive"))
      (node (ref "X18") (pin "16") (pinfunction "S_16") (pintype "passive"))
    )
    (net (code "8") (name "/IO21") (class "Default")
      (node (ref "21X8") (pin "1") (pinfunction "1_1") (pintype "passive"))
      (node (ref "J11") (pin "2") (pinfunction "2_2") (pintype "bidirectional"))
      (node (ref "R11") (pin "P$2") (pinfunction "2_P$2") (pintype "passive"))
      (node (ref "X18") (pin "18") (pinfunction "S_18") (pintype "passive"))
    )
    (net (code "9") (name "/IO37") (class "Default")
      (node (ref "37X9") (pin "1") (pinfunction "1_1") (pintype "passive"))
      (node (ref "J12") (pin "2") (pinfunction "2_2") (pintype "bidirectional"))
      (node (ref "R12") (pin "P$2") (pinfunction "2_P$2") (pintype "passive"))
      (node (ref "X18") (pin "20") (pinfunction "S_20") (pintype "passive"))
    )
    (net (code "10") (name "/IO39") (class "Default")
      (node (ref "39X10") (pin "1") (pinfunction "1_1") (pintype "passive"))
      (node (ref "J14") (pin "2") (pinfunction "2_2") (pintype "bidirectional"))
      (node (ref "R13") (pin "P$2") (pinfunction "2_P$2") (pintype "passive"))
      (node (ref "X18") (pin "22") (pinfunction "S_22") (pintype "passive"))
    )
    (net (code "11") (name "/IO43") (class "Default")
      (node (ref "43X11") (pin "1") (pinfunction "1_1") (pintype "passive"))
      (node (ref "J15") (pin "2") (pinfunction "2_2") (pintype "bidirectional"))
      (node (ref "R14") (pin "P$2") (pinfunction "2_P$2") (pintype "passive"))
      (node (ref "X18") (pin "26") (pinfunction "S_26") (pintype "passive"))
    )
    (net (code "12") (name "/IO45") (class "Default")
      (node (ref "45X12") (pin "1") (pinfunction "1_1") (pintype "passive"))
      (node (ref "J16") (pin "2") (pinfunction "2_2") (pintype "bidirectional"))
      (node (ref "R15") (pin "P$2") (pinfunction "2_P$2") (pintype "passive"))
      (node (ref "X18") (pin "28") (pinfunction "S_28") (pintype "passive"))
    )
    (net (code "13") (name "/IO49") (class "Default")
      (node (ref "49X13") (pin "1") (pinfunction "1_1") (pintype "passive"))
      (node (ref "J17") (pin "2") (pinfunction "2_2") (pintype "bidirectional"))
      (node (ref "R16") (pin "P$2") (pinfunction "2_P$2") (pintype "passive"))
      (node (ref "X17") (pin "2") (pinfunction "S_2") (pintype "passive"))
    )
    (net (code "14") (name "/IO51") (class "Default")
      (node (ref "51X14") (pin "1") (pinfunction "1_1") (pintype "passive"))
      (node (ref "J4") (pin "2") (pinfunction "2_2") (pintype "bidirectional"))
      (node (ref "R4") (pin "P$2") (pinfunction "2_P$2") (pintype "passive"))
      (node (ref "X17") (pin "4") (pinfunction "S_4") (pintype "passive"))
    )
    (net (code "15") (name "/IO55") (class "Default")
      (node (ref "55X15") (pin "1") (pinfunction "1_1") (pintype "passive"))
      (node (ref "J5") (pin "2") (pinfunction "2_2") (pintype "bidirectional"))
      (node (ref "R5") (pin "P$2") (pinfunction "2_P$2") (pintype "passive"))
      (node (ref "X17") (pin "6") (pinfunction "S_6") (pintype "passive"))
    )
    (net (code "16") (name "/IO57") (class "Default")
      (node (ref "57X16") (pin "1") (pinfunction "1_1") (pintype "passive"))
      (node (ref "J6") (pin "2") (pinfunction "2_2") (pintype "bidirectional"))
      (node (ref "R6") (pin "P$2") (pinfunction "2_P$2") (pintype "passive"))
      (node (ref "X17") (pin "8") (pinfunction "S_8") (pintype "passive"))
    )
    (net (code "17") (name "/IO145_IN4") (class "Default")
      (node (ref "VSLUE4") (pin "15") (pinfunction "2A3_15") (pintype "input"))
      (node (ref "VSLUE4") (pin "17") (pinfunction "2A4_17") (pintype "input"))
      (node (ref "X13") (pin "28") (pinfunction "S_28") (pintype "passive"))
    )
    (net (code "18") (name "/IO147_IN3") (class "Default")
      (node (ref "VSLUE4") (pin "11") (pinfunction "2A1_11") (pintype "input"))
      (node (ref "VSLUE4") (pin "13") (pinfunction "2A2_13") (pintype "input"))
      (node (ref "X13") (pin "26") (pinfunction "S_26") (pintype "passive"))
    )
    (net (code "19") (name "/IO159_IN2") (class "Default")
      (node (ref "VSLUE4") (pin "6") (pinfunction "1A3_6") (pintype "input"))
      (node (ref "VSLUE4") (pin "8") (pinfunction "1A4_8") (pintype "input"))
      (node (ref "X13") (pin "22") (pinfunction "S_22") (pintype "passive"))
    )
    (net (code "20") (name "/IO161_IN1") (class "Default")
      (node (ref "VSLUE4") (pin "2") (pinfunction "1A1_2") (pintype "input"))
      (node (ref "VSLUE4") (pin "4") (pinfunction "1A2_4") (pintype "input"))
      (node (ref "X13") (pin "20") (pinfunction "S_20") (pintype "passive"))
    )
    (net (code "21") (name "/IO164_IN4") (class "Default")
      (node (ref "VSLUE3") (pin "15") (pinfunction "2A3_15") (pintype "input"))
      (node (ref "VSLUE3") (pin "17") (pinfunction "2A4_17") (pintype "input"))
      (node (ref "X13") (pin "18") (pinfunction "S_18") (pintype "passive"))
    )
    (net (code "22") (name "/IO167_IN3") (class "Default")
      (node (ref "VSLUE3") (pin "11") (pinfunction "2A1_11") (pintype "input"))
      (node (ref "VSLUE3") (pin "13") (pinfunction "2A2_13") (pintype "input"))
      (node (ref "X13") (pin "16") (pinfunction "S_16") (pintype "passive"))
    )
    (net (code "23") (name "/IO169_IN2") (class "Default")
      (node (ref "VSLUE3") (pin "6") (pinfunction "1A3_6") (pintype "input"))
      (node (ref "VSLUE3") (pin "8") (pinfunction "1A4_8") (pintype "input"))
      (node (ref "X13") (pin "14") (pinfunction "S_14") (pintype "passive"))
    )
    (net (code "24") (name "/IO173_IN1") (class "Default")
      (node (ref "VSLUE3") (pin "2") (pinfunction "1A1_2") (pintype "input"))
      (node (ref "VSLUE3") (pin "4") (pinfunction "1A2_4") (pintype "input"))
      (node (ref "X13") (pin "12") (pinfunction "S_12") (pintype "passive"))
    )
    (net (code "25") (name "/IO174_IN1") (class "Default")
      (node (ref "VSLUE") (pin "2") (pinfunction "1A1_2") (pintype "input"))
      (node (ref "VSLUE") (pin "4") (pinfunction "1A2_4") (pintype "input"))
      (node (ref "X13") (pin "9") (pinfunction "S_9") (pintype "passive"))
    )
    (net (code "26") (name "/IO175_IN1") (class "Default")
      (node (ref "VSLUE2") (pin "2") (pinfunction "1A1_2") (pintype "input"))
      (node (ref "VSLUE2") (pin "4") (pinfunction "1A2_4") (pintype "input"))
      (node (ref "X13") (pin "10") (pinfunction "S_10") (pintype "passive"))
    )
    (net (code "27") (name "/IO176_IN2") (class "Default")
      (node (ref "VSLUE") (pin "6") (pinfunction "1A3_6") (pintype "input"))
      (node (ref "VSLUE") (pin "8") (pinfunction "1A4_8") (pintype "input"))
      (node (ref "X13") (pin "7") (pinfunction "S_7") (pintype "passive"))
    )
    (net (code "28") (name "/IO177_IN2") (class "Default")
      (node (ref "VSLUE2") (pin "6") (pinfunction "1A3_6") (pintype "input"))
      (node (ref "VSLUE2") (pin "8") (pinfunction "1A4_8") (pintype "input"))
      (node (ref "X13") (pin "8") (pinfunction "S_8") (pintype "passive"))
    )
    (net (code "29") (name "/IO181_IN3") (class "Default")
      (node (ref "VSLUE") (pin "11") (pinfunction "2A1_11") (pintype "input"))
      (node (ref "VSLUE") (pin "13") (pinfunction "2A2_13") (pintype "input"))
      (node (ref "X13") (pin "5") (pinfunction "S_5") (pintype "passive"))
    )
    (net (code "30") (name "/IO182_IN3") (class "Default")
      (node (ref "VSLUE2") (pin "11") (pinfunction "2A1_11") (pintype "input"))
      (node (ref "VSLUE2") (pin "13") (pinfunction "2A2_13") (pintype "input"))
      (node (ref "X13") (pin "6") (pinfunction "S_6") (pintype "passive"))
    )
    (net (code "31") (name "/IO183_IN4") (class "Default")
      (node (ref "VSLUE") (pin "15") (pinfunction "2A3_15") (pintype "input"))
      (node (ref "VSLUE") (pin "17") (pinfunction "2A4_17") (pintype "input"))
      (node (ref "X13") (pin "3") (pinfunction "S_3") (pintype "passive"))
    )
    (net (code "32") (name "/IO184_IN4") (class "Default")
      (node (ref "VSLUE2") (pin "15") (pinfunction "2A3_15") (pintype "input"))
      (node (ref "VSLUE2") (pin "17") (pinfunction "2A4_17") (pintype "input"))
      (node (ref "X13") (pin "4") (pinfunction "S_4") (pintype "passive"))
    )
    (net (code "33") (name "/IO185") (class "Default")
      (node (ref "J18") (pin "8") (pinfunction "8_8") (pintype "passive"))
      (node (ref "X15") (pin "16") (pinfunction "S_16") (pintype "passive"))
    )
    (net (code "34") (name "/IO187") (class "Default")
      (node (ref "J18") (pin "7") (pinfunction "7_7") (pintype "passive"))
      (node (ref "X15") (pin "14") (pinfunction "S_14") (pintype "passive"))
    )
    (net (code "35") (name "/IO189") (class "Default")
      (node (ref "J18") (pin "6") (pinfunction "6_6") (pintype "passive"))
      (node (ref "X15") (pin "12") (pinfunction "S_12") (pintype "passive"))
    )
    (net (code "36") (name "/IO195") (class "Default")
      (node (ref "J18") (pin "5") (pinfunction "5_5") (pintype "passive"))
      (node (ref "X15") (pin "10") (pinfunction "S_10") (pintype "passive"))
    )
    (net (code "37") (name "/IO197") (class "Default")
      (node (ref "J18") (pin "4") (pinfunction "4_4") (pintype "passive"))
      (node (ref "X15") (pin "8") (pinfunction "S_8") (pintype "passive"))
    )
    (net (code "38") (name "/IO199") (class "Default")
      (node (ref "J18") (pin "3") (pinfunction "3_3") (pintype "passive"))
      (node (ref "X15") (pin "6") (pinfunction "S_6") (pintype "passive"))
    )
    (net (code "39") (name "/IO201") (class "Default")
      (node (ref "J18") (pin "2") (pinfunction "2_2") (pintype "passive"))
      (node (ref "X15") (pin "4") (pinfunction "S_4") (pintype "passive"))
    )
    (net (code "40") (name "/IO203") (class "Default")
      (node (ref "J18") (pin "1") (pinfunction "1_1") (pintype "passive"))
      (node (ref "X15") (pin "2") (pinfunction "S_2") (pintype "passive"))
    )
    (net (code "41") (name "/IO236") (class "Default")
      (node (ref "236X1") (pin "1") (pinfunction "1_1") (pintype "passive"))
      (node (ref "J1") (pin "2") (pinfunction "2_2") (pintype "bidirectional"))
      (node (ref "R1") (pin "P$2") (pinfunction "2_P$2") (pintype "passive"))
      (node (ref "X18") (pin "4") (pinfunction "S_4") (pintype "passive"))
    )
    (net (code "42") (name "/IO238") (class "Default")
      (node (ref "238X2") (pin "1") (pinfunction "1_1") (pintype "passive"))
      (node (ref "J2") (pin "2") (pinfunction "2_2") (pintype "bidirectional"))
      (node (ref "R2") (pin "P$2") (pinfunction "2_P$2") (pintype "passive"))
      (node (ref "X18") (pin "6") (pinfunction "S_6") (pintype "passive"))
    )
    (net (code "43") (name "/IO240") (class "Default")
      (node (ref "240X3") (pin "1") (pinfunction "1_1") (pintype "passive"))
      (node (ref "J3") (pin "2") (pinfunction "2_2") (pintype "bidirectional"))
      (node (ref "R3") (pin "P$2") (pinfunction "2_P$2") (pintype "passive"))
      (node (ref "X18") (pin "8") (pinfunction "S_8") (pintype "passive"))
    )
    (net (code "44") (name "/OUT1") (class "Default")
      (node (ref "174OUT1") (pin "1") (pinfunction "1_1") (pintype "passive"))
      (node (ref "OJ1") (pin "1") (pinfunction "1_1") (pintype "bidirectional"))
      (node (ref "VSLUE") (pin "16") (pinfunction "1Y2_16") (pintype "output"))
      (node (ref "VSLUE") (pin "18") (pinfunction "1Y1_18") (pintype "output"))
    )
    (net (code "45") (name "/OUT2") (class "Default")
      (node (ref "176OUT2") (pin "1") (pinfunction "1_1") (pintype "passive"))
      (node (ref "OJ2") (pin "1") (pinfunction "1_1") (pintype "bidirectional"))
      (node (ref "VSLUE") (pin "12") (pinfunction "1Y4_12") (pintype "output"))
      (node (ref "VSLUE") (pin "14") (pinfunction "1Y3_14") (pintype "output"))
    )
    (net (code "46") (name "/OUT3") (class "Default")
      (node (ref "181OUT3") (pin "1") (pinfunction "1_1") (pintype "passive"))
      (node (ref "OJ3") (pin "1") (pinfunction "1_1") (pintype "bidirectional"))
      (node (ref "VSLUE") (pin "7") (pinfunction "2Y2_7") (pintype "output"))
      (node (ref "VSLUE") (pin "9") (pinfunction "2Y1_9") (pintype "output"))
    )
    (net (code "47") (name "/OUT4") (class "Default")
      (node (ref "183OUT4") (pin "1") (pinfunction "1_1") (pintype "passive"))
      (node (ref "OJ4") (pin "1") (pinfunction "1_1") (pintype "bidirectional"))
      (node (ref "VSLUE") (pin "3") (pinfunction "2Y4_3") (pintype "output"))
      (node (ref "VSLUE") (pin "5") (pinfunction "2Y3_5") (pintype "output"))
    )
    (net (code "48") (name "/OUT5") (class "Default")
      (node (ref "175OUT5") (pin "1") (pinfunction "1_1") (pintype "passive"))
      (node (ref "OJ12") (pin "1") (pinfunction "1_1") (pintype "bidirectional"))
      (node (ref "VSLUE2") (pin "16") (pinfunction "1Y2_16") (pintype "output"))
      (node (ref "VSLUE2") (pin "18") (pinfunction "1Y1_18") (pintype "output"))
    )
    (net (code "49") (name "/OUT6") (class "Default")
      (node (ref "177OUT6") (pin "1") (pinfunction "1_1") (pintype "passive"))
      (node (ref "OJ11") (pin "1") (pinfunction "1_1") (pintype "bidirectional"))
      (node (ref "VSLUE2") (pin "12") (pinfunction "1Y4_12") (pintype "output"))
      (node (ref "VSLUE2") (pin "14") (pinfunction "1Y3_14") (pintype "output"))
    )
    (net (code "50") (name "/OUT7") (class "Default")
      (node (ref "182OUT7") (pin "1") (pinfunction "1_1") (pintype "passive"))
      (node (ref "OJ10") (pin "1") (pinfunction "1_1") (pintype "bidirectional"))
      (node (ref "VSLUE2") (pin "7") (pinfunction "2Y2_7") (pintype "output"))
      (node (ref "VSLUE2") (pin "9") (pinfunction "2Y1_9") (pintype "output"))
    )
    (net (code "51") (name "/OUT8") (class "Default")
      (node (ref "184OUT8") (pin "1") (pinfunction "1_1") (pintype "passive"))
      (node (ref "OJ9") (pin "1") (pinfunction "1_1") (pintype "bidirectional"))
      (node (ref "VSLUE2") (pin "3") (pinfunction "2Y4_3") (pintype "output"))
      (node (ref "VSLUE2") (pin "5") (pinfunction "2Y3_5") (pintype "output"))
    )
    (net (code "52") (name "/OUT9") (class "Default")
      (node (ref "173OUT9") (pin "1") (pinfunction "1_1") (pintype "passive"))
      (node (ref "OJ16") (pin "1") (pinfunction "1_1") (pintype "bidirectional"))
      (node (ref "VSLUE3") (pin "16") (pinfunction "1Y2_16") (pintype "output"))
      (node (ref "VSLUE3") (pin "18") (pinfunction "1Y1_18") (pintype "output"))
    )
    (net (code "53") (name "/OUT10") (class "Default")
      (node (ref "169OUT10") (pin "1") (pinfunction "1_1") (pintype "passive"))
      (node (ref "OJ15") (pin "1") (pinfunction "1_1") (pintype "bidirectional"))
      (node (ref "VSLUE3") (pin "12") (pinfunction "1Y4_12") (pintype "output"))
      (node (ref "VSLUE3") (pin "14") (pinfunction "1Y3_14") (pintype "output"))
    )
    (net (code "54") (name "/OUT11") (class "Default")
      (node (ref "167OUT11") (pin "1") (pinfunction "1_1") (pintype "passive"))
      (node (ref "OJ14") (pin "1") (pinfunction "1_1") (pintype "bidirectional"))
      (node (ref "VSLUE3") (pin "7") (pinfunction "2Y2_7") (pintype "output"))
      (node (ref "VSLUE3") (pin "9") (pinfunction "2Y1_9") (pintype "output"))
    )
    (net (code "55") (name "/OUT12") (class "Default")
      (node (ref "164OUT12") (pin "1") (pinfunction "1_1") (pintype "passive"))
      (node (ref "OJ13") (pin "1") (pinfunction "1_1") (pintype "bidirectional"))
      (node (ref "VSLUE3") (pin "3") (pinfunction "2Y4_3") (pintype "output"))
      (node (ref "VSLUE3") (pin "5") (pinfunction "2Y3_5") (pintype "output"))
    )
    (net (code "56") (name "/OUT13") (class "Default")
      (node (ref "161OUT13") (pin "1") (pinfunction "1_1") (pintype "passive"))
      (node (ref "OJ20") (pin "1") (pinfunction "1_1") (pintype "bidirectional"))
      (node (ref "VSLUE4") (pin "16") (pinfunction "1Y2_16") (pintype "output"))
      (node (ref "VSLUE4") (pin "18") (pinfunction "1Y1_18") (pintype "output"))
    )
    (net (code "57") (name "/OUT14") (class "Default")
      (node (ref "159OUT14") (pin "1") (pinfunction "1_1") (pintype "passive"))
      (node (ref "OJ19") (pin "1") (pinfunction "1_1") (pintype "bidirectional"))
      (node (ref "VSLUE4") (pin "12") (pinfunction "1Y4_12") (pintype "output"))
      (node (ref "VSLUE4") (pin "14") (pinfunction "1Y3_14") (pintype "output"))
    )
    (net (code "58") (name "/OUT15") (class "Default")
      (node (ref "147OUT15") (pin "1") (pinfunction "1_1") (pintype "passive"))
      (node (ref "OJ18") (pin "1") (pinfunction "1_1") (pintype "bidirectional"))
      (node (ref "VSLUE4") (pin "7") (pinfunction "2Y2_7") (pintype "output"))
      (node (ref "VSLUE4") (pin "9") (pinfunction "2Y1_9") (pintype "output"))
    )
    (net (code "59") (name "/OUT16") (class "Default")
      (node (ref "145OUT16") (pin "1") (pinfunction "1_1") (pintype "passive"))
      (node (ref "OJ17") (pin "1") (pinfunction "1_1") (pintype "bidirectional"))
      (node (ref "VSLUE4") (pin "3") (pinfunction "2Y4_3") (pintype "output"))
      (node (ref "VSLUE4") (pin "5") (pinfunction "2Y3_5") (pintype "output"))
    )
    (net (code "60") (name "unconnected-(J13-Pad1)") (class "Default")
      (node (ref "J13") (pin "1") (pinfunction "1_1") (pintype "passive"))
    )
    (net (code "61") (name "unconnected-(J13-Pad2)") (class "Default")
      (node (ref "J13") (pin "2") (pinfunction "2_2") (pintype "passive"))
    )
    (net (code "62") (name "unconnected-(J13-Pad3)") (class "Default")
      (node (ref "J13") (pin "3") (pinfunction "3_3") (pintype "passive"))
    )
    (net (code "63") (name "unconnected-(J13-Pad4)") (class "Default")
      (node (ref "J13") (pin "4") (pinfunction "4_4") (pintype "passive"))
    )
    (net (code "64") (name "unconnected-(X13C-S-Pad11)") (class "Default")
      (node (ref "X13") (pin "11") (pinfunction "S_11") (pintype "passive"))
    )
    (net (code "65") (name "unconnected-(X13E-S-Pad13)") (class "Default")
      (node (ref "X13") (pin "13") (pinfunction "S_13") (pintype "passive"))
    )
    (net (code "66") (name "unconnected-(X13G-S-Pad15)") (class "Default")
      (node (ref "X13") (pin "15") (pinfunction "S_15") (pintype "passive"))
    )
    (net (code "67") (name "unconnected-(X13I-S-Pad17)") (class "Default")
      (node (ref "X13") (pin "17") (pinfunction "S_17") (pintype "passive"))
    )
    (net (code "68") (name "unconnected-(X13K-S-Pad19)") (class "Default")
      (node (ref "X13") (pin "19") (pinfunction "S_19") (pintype "passive"))
    )
    (net (code "69") (name "unconnected-(X13N-S-Pad21)") (class "Default")
      (node (ref "X13") (pin "21") (pinfunction "S_21") (pintype "passive"))
    )
    (net (code "70") (name "unconnected-(X13R-S-Pad25)") (class "Default")
      (node (ref "X13") (pin "25") (pinfunction "S_25") (pintype "passive"))
    )
    (net (code "71") (name "unconnected-(X13T-S-Pad27)") (class "Default")
      (node (ref "X13") (pin "27") (pinfunction "S_27") (pintype "passive"))
    )
    (net (code "72") (name "unconnected-(X14A-S-Pad1)") (class "Default")
      (node (ref "X14") (pin "1") (pinfunction "S_1") (pintype "passive"))
    )
    (net (code "73") (name "unconnected-(X14AA-S-Pad8)") (class "Default")
      (node (ref "X14") (pin "8") (pinfunction "S_8") (pintype "passive"))
    )
    (net (code "74") (name "unconnected-(X14AB-S-Pad9)") (class "Default")
      (node (ref "X14") (pin "9") (pinfunction "S_9") (pintype "passive"))
    )
    (net (code "75") (name "unconnected-(X14B-S-Pad10)") (class "Default")
      (node (ref "X14") (pin "10") (pinfunction "S_10") (pintype "passive"))
    )
    (net (code "76") (name "unconnected-(X14C-S-Pad11)") (class "Default")
      (node (ref "X14") (pin "11") (pinfunction "S_11") (pintype "passive"))
    )
    (net (code "77") (name "unconnected-(X14D-S-Pad12)") (class "Default")
      (node (ref "X14") (pin "12") (pinfunction "S_12") (pintype "passive"))
    )
    (net (code "78") (name "unconnected-(X14E-S-Pad13)") (class "Default")
      (node (ref "X14") (pin "13") (pinfunction "S_13") (pintype "passive"))
    )
    (net (code "79") (name "unconnected-(X14F-S-Pad14)") (class "Default")
      (node (ref "X14") (pin "14") (pinfunction "S_14") (pintype "passive"))
    )
    (net (code "80") (name "unconnected-(X14G-S-Pad15)") (class "Default")
      (node (ref "X14") (pin "15") (pinfunction "S_15") (pintype "passive"))
    )
    (net (code "81") (name "unconnected-(X14H-S-Pad16)") (class "Default")
      (node (ref "X14") (pin "16") (pinfunction "S_16") (pintype "passive"))
    )
    (net (code "82") (name "unconnected-(X14I-S-Pad17)") (class "Default")
      (node (ref "X14") (pin "17") (pinfunction "S_17") (pintype "passive"))
    )
    (net (code "83") (name "unconnected-(X14J-S-Pad18)") (class "Default")
      (node (ref "X14") (pin "18") (pinfunction "S_18") (pintype "passive"))
    )
    (net (code "84") (name "unconnected-(X14K-S-Pad19)") (class "Default")
      (node (ref "X14") (pin "19") (pinfunction "S_19") (pintype "passive"))
    )
    (net (code "85") (name "unconnected-(X14L-S-Pad2)") (class "Default")
      (node (ref "X14") (pin "2") (pinfunction "S_2") (pintype "passive"))
    )
    (net (code "86") (name "unconnected-(X14M-S-Pad20)") (class "Default")
      (node (ref "X14") (pin "20") (pinfunction "S_20") (pintype "passive"))
    )
    (net (code "87") (name "unconnected-(X14N-S-Pad21)") (class "Default")
      (node (ref "X14") (pin "21") (pinfunction "S_21") (pintype "passive"))
    )
    (net (code "88") (name "unconnected-(X14O-S-Pad22)") (class "Default")
      (node (ref "X14") (pin "22") (pinfunction "S_22") (pintype "passive"))
    )
    (net (code "89") (name "unconnected-(X14P-S-Pad23)") (class "Default")
      (node (ref "X14") (pin "23") (pinfunction "S_23") (pintype "passive"))
    )
    (net (code "90") (name "unconnected-(X14Q-S-Pad24)") (class "Default")
      (node (ref "X14") (pin "24") (pinfunction "S_24") (pintype "passive"))
    )
    (net (code "91") (name "unconnected-(X14R-S-Pad25)") (class "Default")
      (node (ref "X14") (pin "25") (pinfunction "S_25") (pintype "passive"))
    )
    (net (code "92") (name "unconnected-(X14S-S-Pad26)") (class "Default")
      (node (ref "X14") (pin "26") (pinfunction "S_26") (pintype "passive"))
    )
    (net (code "93") (name "unconnected-(X14T-S-Pad27)") (class "Default")
      (node (ref "X14") (pin "27") (pinfunction "S_27") (pintype "passive"))
    )
    (net (code "94") (name "unconnected-(X14U-S-Pad28)") (class "Default")
      (node (ref "X14") (pin "28") (pinfunction "S_28") (pintype "passive"))
    )
    (net (code "95") (name "unconnected-(X14V-S-Pad3)") (class "Default")
      (node (ref "X14") (pin "3") (pinfunction "S_3") (pintype "passive"))
    )
    (net (code "96") (name "unconnected-(X14W-S-Pad4)") (class "Default")
      (node (ref "X14") (pin "4") (pinfunction "S_4") (pintype "passive"))
    )
    (net (code "97") (name "unconnected-(X14X-S-Pad5)") (class "Default")
      (node (ref "X14") (pin "5") (pinfunction "S_5") (pintype "passive"))
    )
    (net (code "98") (name "unconnected-(X14Y-S-Pad6)") (class "Default")
      (node (ref "X14") (pin "6") (pinfunction "S_6") (pintype "passive"))
    )
    (net (code "99") (name "unconnected-(X14Z-S-Pad7)") (class "Default")
      (node (ref "X14") (pin "7") (pinfunction "S_7") (pintype "passive"))
    )
    (net (code "100") (name "unconnected-(X15A-S-Pad1)") (class "Default")
      (node (ref "X15") (pin "1") (pinfunction "S_1") (pintype "passive"))
    )
    (net (code "101") (name "unconnected-(X15C-S-Pad11)") (class "Default")
      (node (ref "X15") (pin "11") (pinfunction "S_11") (pintype "passive"))
    )
    (net (code "102") (name "unconnected-(X15E-S-Pad13)") (class "Default")
      (node (ref "X15") (pin "13") (pinfunction "S_13") (pintype "passive"))
    )
    (net (code "103") (name "unconnected-(X15G-S-Pad15)") (class "Default")
      (node (ref "X15") (pin "15") (pinfunction "S_15") (pintype "passive"))
    )
    (net (code "104") (name "unconnected-(X15J-S-Pad3)") (class "Default")
      (node (ref "X15") (pin "3") (pinfunction "S_3") (pintype "passive"))
    )
    (net (code "105") (name "unconnected-(X15L-S-Pad5)") (class "Default")
      (node (ref "X15") (pin "5") (pinfunction "S_5") (pintype "passive"))
    )
    (net (code "106") (name "unconnected-(X15N-S-Pad7)") (class "Default")
      (node (ref "X15") (pin "7") (pinfunction "S_7") (pintype "passive"))
    )
    (net (code "107") (name "unconnected-(X15P-S-Pad9)") (class "Default")
      (node (ref "X15") (pin "9") (pinfunction "S_9") (pintype "passive"))
    )
    (net (code "108") (name "unconnected-(X16A-S-Pad1)") (class "Default")
      (node (ref "X16") (pin "1") (pinfunction "S_1") (pintype "passive"))
    )
    (net (code "109") (name "unconnected-(X16B-S-Pad10)") (class "Default")
      (node (ref "X16") (pin "10") (pinfunction "S_10") (pintype "passive"))
    )
    (net (code "110") (name "unconnected-(X16C-S-Pad11)") (class "Default")
      (node (ref "X16") (pin "11") (pinfunction "S_11") (pintype "passive"))
    )
    (net (code "111") (name "unconnected-(X16D-S-Pad12)") (class "Default")
      (node (ref "X16") (pin "12") (pinfunction "S_12") (pintype "passive"))
    )
    (net (code "112") (name "unconnected-(X16E-S-Pad13)") (class "Default")
      (node (ref "X16") (pin "13") (pinfunction "S_13") (pintype "passive"))
    )
    (net (code "113") (name "unconnected-(X16F-S-Pad14)") (class "Default")
      (node (ref "X16") (pin "14") (pinfunction "S_14") (pintype "passive"))
    )
    (net (code "114") (name "unconnected-(X16G-S-Pad15)") (class "Default")
      (node (ref "X16") (pin "15") (pinfunction "S_15") (pintype "passive"))
    )
    (net (code "115") (name "unconnected-(X16H-S-Pad16)") (class "Default")
      (node (ref "X16") (pin "16") (pinfunction "S_16") (pintype "passive"))
    )
    (net (code "116") (name "unconnected-(X16I-S-Pad2)") (class "Default")
      (node (ref "X16") (pin "2") (pinfunction "S_2") (pintype "passive"))
    )
    (net (code "117") (name "unconnected-(X16J-S-Pad3)") (class "Default")
      (node (ref "X16") (pin "3") (pinfunction "S_3") (pintype "passive"))
    )
    (net (code "118") (name "unconnected-(X16K-S-Pad4)") (class "Default")
      (node (ref "X16") (pin "4") (pinfunction "S_4") (pintype "passive"))
    )
    (net (code "119") (name "unconnected-(X16L-S-Pad5)") (class "Default")
      (node (ref "X16") (pin "5") (pinfunction "S_5") (pintype "passive"))
    )
    (net (code "120") (name "unconnected-(X16M-S-Pad6)") (class "Default")
      (node (ref "X16") (pin "6") (pinfunction "S_6") (pintype "passive"))
    )
    (net (code "121") (name "unconnected-(X16N-S-Pad7)") (class "Default")
      (node (ref "X16") (pin "7") (pinfunction "S_7") (pintype "passive"))
    )
    (net (code "122") (name "unconnected-(X16O-S-Pad8)") (class "Default")
      (node (ref "X16") (pin "8") (pinfunction "S_8") (pintype "passive"))
    )
    (net (code "123") (name "unconnected-(X16P-S-Pad9)") (class "Default")
      (node (ref "X16") (pin "9") (pinfunction "S_9") (pintype "passive"))
    )
    (net (code "124") (name "unconnected-(X17A-S-Pad1)") (class "Default")
      (node (ref "X17") (pin "1") (pinfunction "S_1") (pintype "passive"))
    )
    (net (code "125") (name "unconnected-(X17AB-S-Pad9)") (class "Default")
      (node (ref "X17") (pin "9") (pinfunction "S_9") (pintype "passive"))
    )
    (net (code "126") (name "unconnected-(X17B-S-Pad10)") (class "Default")
      (node (ref "X17") (pin "10") (pinfunction "S_10") (pintype "passive"))
    )
    (net (code "127") (name "unconnected-(X17C-S-Pad11)") (class "Default")
      (node (ref "X17") (pin "11") (pinfunction "S_11") (pintype "passive"))
    )
    (net (code "128") (name "unconnected-(X17D-S-Pad12)") (class "Default")
      (node (ref "X17") (pin "12") (pinfunction "S_12") (pintype "passive"))
    )
    (net (code "129") (name "unconnected-(X17E-S-Pad13)") (class "Default")
      (node (ref "X17") (pin "13") (pinfunction "S_13") (pintype "passive"))
    )
    (net (code "130") (name "unconnected-(X17F-S-Pad14)") (class "Default")
      (node (ref "X17") (pin "14") (pinfunction "S_14") (pintype "passive"))
    )
    (net (code "131") (name "unconnected-(X17G-S-Pad15)") (class "Default")
      (node (ref "X17") (pin "15") (pinfunction "S_15") (pintype "passive"))
    )
    (net (code "132") (name "unconnected-(X17H-S-Pad16)") (class "Default")
      (node (ref "X17") (pin "16") (pinfunction "S_16") (pintype "passive"))
    )
    (net (code "133") (name "unconnected-(X17I-S-Pad17)") (class "Default")
      (node (ref "X17") (pin "17") (pinfunction "S_17") (pintype "passive"))
    )
    (net (code "134") (name "unconnected-(X17J-S-Pad18)") (class "Default")
      (node (ref "X17") (pin "18") (pinfunction "S_18") (pintype "passive"))
    )
    (net (code "135") (name "unconnected-(X17K-S-Pad19)") (class "Default")
      (node (ref "X17") (pin "19") (pinfunction "S_19") (pintype "passive"))
    )
    (net (code "136") (name "unconnected-(X17M-S-Pad20)") (class "Default")
      (node (ref "X17") (pin "20") (pinfunction "S_20") (pintype "passive"))
    )
    (net (code "137") (name "unconnected-(X17N-S-Pad21)") (class "Default")
      (node (ref "X17") (pin "21") (pinfunction "S_21") (pintype "passive"))
    )
    (net (code "138") (name "unconnected-(X17O-S-Pad22)") (class "Default")
      (node (ref "X17") (pin "22") (pinfunction "S_22") (pintype "passive"))
    )
    (net (code "139") (name "unconnected-(X17P-S-Pad23)") (class "Default")
      (node (ref "X17") (pin "23") (pinfunction "S_23") (pintype "passive"))
    )
    (net (code "140") (name "unconnected-(X17Q-S-Pad24)") (class "Default")
      (node (ref "X17") (pin "24") (pinfunction "S_24") (pintype "passive"))
    )
    (net (code "141") (name "unconnected-(X17R-S-Pad25)") (class "Default")
      (node (ref "X17") (pin "25") (pinfunction "S_25") (pintype "passive"))
    )
    (net (code "142") (name "unconnected-(X17S-S-Pad26)") (class "Default")
      (node (ref "X17") (pin "26") (pinfunction "S_26") (pintype "passive"))
    )
    (net (code "143") (name "unconnected-(X17T-S-Pad27)") (class "Default")
      (node (ref "X17") (pin "27") (pinfunction "S_27") (pintype "passive"))
    )
    (net (code "144") (name "unconnected-(X17U-S-Pad28)") (class "Default")
      (node (ref "X17") (pin "28") (pinfunction "S_28") (pintype "passive"))
    )
    (net (code "145") (name "unconnected-(X17V-S-Pad3)") (class "Default")
      (node (ref "X17") (pin "3") (pinfunction "S_3") (pintype "passive"))
    )
    (net (code "146") (name "unconnected-(X17X-S-Pad5)") (class "Default")
      (node (ref "X17") (pin "5") (pinfunction "S_5") (pintype "passive"))
    )
    (net (code "147") (name "unconnected-(X17Z-S-Pad7)") (class "Default")
      (node (ref "X17") (pin "7") (pinfunction "S_7") (pintype "passive"))
    )
    (net (code "148") (name "unconnected-(X18AB-S-Pad9)") (class "Default")
      (node (ref "X18") (pin "9") (pinfunction "S_9") (pintype "passive"))
    )
    (net (code "149") (name "unconnected-(X18C-S-Pad11)") (class "Default")
      (node (ref "X18") (pin "11") (pinfunction "S_11") (pintype "passive"))
    )
    (net (code "150") (name "unconnected-(X18E-S-Pad13)") (class "Default")
      (node (ref "X18") (pin "13") (pinfunction "S_13") (pintype "passive"))
    )
    (net (code "151") (name "unconnected-(X18G-S-Pad15)") (class "Default")
      (node (ref "X18") (pin "15") (pinfunction "S_15") (pintype "passive"))
    )
    (net (code "152") (name "unconnected-(X18I-S-Pad17)") (class "Default")
      (node (ref "X18") (pin "17") (pinfunction "S_17") (pintype "passive"))
    )
    (net (code "153") (name "unconnected-(X18K-S-Pad19)") (class "Default")
      (node (ref "X18") (pin "19") (pinfunction "S_19") (pintype "passive"))
    )
    (net (code "154") (name "unconnected-(X18L-S-Pad2)") (class "Default")
      (node (ref "X18") (pin "2") (pinfunction "S_2") (pintype "passive"))
    )
    (net (code "155") (name "unconnected-(X18N-S-Pad21)") (class "Default")
      (node (ref "X18") (pin "21") (pinfunction "S_21") (pintype "passive"))
    )
    (net (code "156") (name "unconnected-(X18R-S-Pad25)") (class "Default")
      (node (ref "X18") (pin "25") (pinfunction "S_25") (pintype "passive"))
    )
    (net (code "157") (name "unconnected-(X18T-S-Pad27)") (class "Default")
      (node (ref "X18") (pin "27") (pinfunction "S_27") (pintype "passive"))
    )
    (net (code "158") (name "unconnected-(X18V-S-Pad3)") (class "Default")
      (node (ref "X18") (pin "3") (pinfunction "S_3") (pintype "passive"))
    )
    (net (code "159") (name "unconnected-(X18X-S-Pad5)") (class "Default")
      (node (ref "X18") (pin "5") (pinfunction "S_5") (pintype "passive"))
    )
    (net (code "160") (name "unconnected-(X18Z-S-Pad7)") (class "Default")
      (node (ref "X18") (pin "7") (pinfunction "S_7") (pintype "passive"))
    )
  )
)
